# UP02513040.net
KiCad netlist of a schematic drawn in Altium Designer
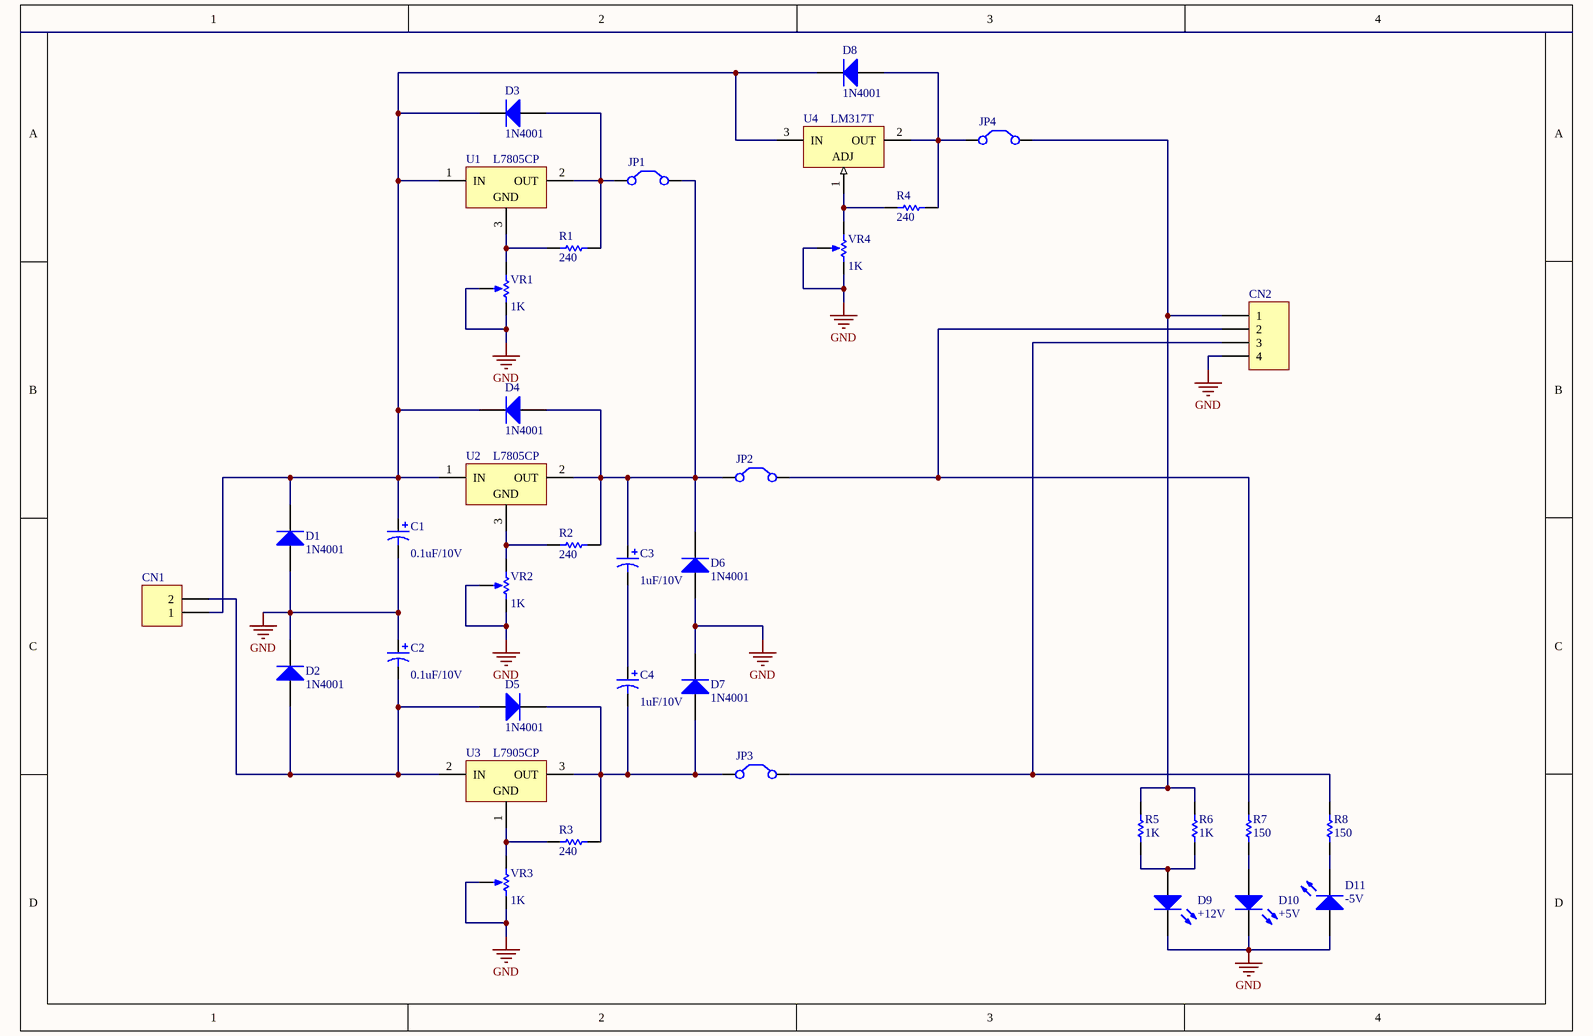
[diagram p0: UP02513040.SchDoc]

(export (version "E")
  (design (tool "Eeschema 10.0.6"))
  (components
    (comp (ref "C1")
      (value "0.1uF/10V")
      (footprint "RB7.6-15")
      (description "Polarized Capacitor (Radial)")
      (fields (field (name "Comment") "Cap Pol1") (field (name "PUBLISHER") "Altium Limited"))
      (libsource (lib "Miscellaneous Devices") (part "Cap Pol1"))
    )
    (comp (ref "C2")
      (value "0.1uF/10V")
      (footprint "RB7.6-15")
      (description "Polarized Capacitor (Radial)")
      (fields (field (name "Comment") "Cap Pol1") (field (name "PUBLISHER") "Altium Limited"))
      (libsource (lib "Miscellaneous Devices") (part "Cap Pol1"))
    )
    (comp (ref "C3")
      (value "1uF/10V")
      (footprint "RB7.6-15")
      (description "Polarized Capacitor (Radial)")
      (fields (field (name "Comment") "Cap Pol1") (field (name "PUBLISHER") "Altium Limited"))
      (libsource (lib "Miscellaneous Devices") (part "Cap Pol1"))
    )
    (comp (ref "C4")
      (value "1uF/10V")
      (footprint "RB7.6-15")
      (description "Polarized Capacitor (Radial)")
      (fields (field (name "Comment") "Cap Pol1") (field (name "PUBLISHER") "Altium Limited"))
      (libsource (lib "Miscellaneous Devices") (part "Cap Pol1"))
    )
    (comp (ref "CN1")
      (value "Header 2H")
      (footprint "HDR1X2H")
      (description "Header, 2-Pin, Right Angle")
      (fields
        (field (name "MANUFACTURER") "PHOENIX CONTACT")
        (field (name "MANUFACTURER PART NUMBER") "1725656")
        (field (name "PUBLISHER") "Altium Limited")
      )
      (libsource (lib "Miscellaneous Connectors") (part "Header 2H"))
    )
    (comp (ref "CN2")
      (value "Header 4H")
      (footprint "HDR1X4H")
      (description "Header, 4-Pin, Right Angle")
      (fields (field (name "PUBLISHER") "Altium Limited"))
      (libsource (lib "Miscellaneous Connectors") (part "Header 4H"))
    )
    (comp (ref "D1")
      (value "1N4001")
      (footprint "DO-41")
      (description "1 Amp General Purpose Rectifier")
      (fields
        (field (name "MANUFACTURER") "Micro Commercial Co")
        (field (name "MANUFACTURER PART NUMBER") "1N4001-TP")
        (field (name "PUBLISHER") "Altium Limited")
      )
      (libsource (lib "Miscellaneous Devices") (part "Diode 1N4001"))
    )
    (comp (ref "D2")
      (value "1N4001")
      (footprint "DO-41")
      (description "1 Amp General Purpose Rectifier")
      (fields
        (field (name "MANUFACTURER") "Micro Commercial Co")
        (field (name "MANUFACTURER PART NUMBER") "1N4001-TP")
        (field (name "PUBLISHER") "Altium Limited")
      )
      (libsource (lib "Miscellaneous Devices") (part "Diode 1N4001"))
    )
    (comp (ref "D3")
      (value "1N4001")
      (footprint "DO-41")
      (description "1 Amp General Purpose Rectifier")
      (fields
        (field (name "MANUFACTURER") "Micro Commercial Co")
        (field (name "MANUFACTURER PART NUMBER") "1N4001-TP")
        (field (name "PUBLISHER") "Altium Limited")
      )
      (libsource (lib "Miscellaneous Devices") (part "Diode 1N4001"))
    )
    (comp (ref "D4")
      (value "1N4001")
      (footprint "DO-41")
      (description "1 Amp General Purpose Rectifier")
      (fields
        (field (name "MANUFACTURER") "Micro Commercial Co")
        (field (name "MANUFACTURER PART NUMBER") "1N4001-TP")
        (field (name "PUBLISHER") "Altium Limited")
      )
      (libsource (lib "Miscellaneous Devices") (part "Diode 1N4001"))
    )
    (comp (ref "D5")
      (value "1N4001")
      (footprint "DO-41")
      (description "1 Amp General Purpose Rectifier")
      (fields
        (field (name "MANUFACTURER") "Micro Commercial Co")
        (field (name "MANUFACTURER PART NUMBER") "1N4001-TP")
        (field (name "PUBLISHER") "Altium Limited")
      )
      (libsource (lib "Miscellaneous Devices") (part "Diode 1N4001"))
    )
    (comp (ref "D6")
      (value "1N4001")
      (footprint "DO-41")
      (description "1 Amp General Purpose Rectifier")
      (fields
        (field (name "MANUFACTURER") "Micro Commercial Co")
        (field (name "MANUFACTURER PART NUMBER") "1N4001-TP")
        (field (name "PUBLISHER") "Altium Limited")
      )
      (libsource (lib "Miscellaneous Devices") (part "Diode 1N4001"))
    )
    (comp (ref "D7")
      (value "1N4001")
      (footprint "DO-41")
      (description "1 Amp General Purpose Rectifier")
      (fields
        (field (name "MANUFACTURER") "Micro Commercial Co")
        (field (name "MANUFACTURER PART NUMBER") "1N4001-TP")
        (field (name "PUBLISHER") "Altium Limited")
      )
      (libsource (lib "Miscellaneous Devices") (part "Diode 1N4001"))
    )
    (comp (ref "D8")
      (value "1N4001")
      (footprint "DO-41")
      (description "1 Amp General Purpose Rectifier")
      (fields
        (field (name "MANUFACTURER") "Micro Commercial Co")
        (field (name "MANUFACTURER PART NUMBER") "1N4001-TP")
        (field (name "PUBLISHER") "Altium Limited")
      )
      (libsource (lib "Miscellaneous Devices") (part "Diode 1N4001"))
    )
    (comp (ref "D9")
      (value "+12V")
      (footprint "LED-0")
      (description "Typical INFRARED GaAs LED")
      (fields
        (field (name "MANUFACTURER") "MULTICOMP")
        (field (name "MANUFACTURER PART NUMBER") "OVL-3324")
        (field (name "PUBLISHER") "Altium Limited")
      )
      (libsource (lib "Miscellaneous Devices") (part "LED0"))
    )
    (comp (ref "D10")
      (value "+5V")
      (footprint "LED-0")
      (description "Typical INFRARED GaAs LED")
      (fields
        (field (name "MANUFACTURER") "MULTICOMP")
        (field (name "MANUFACTURER PART NUMBER") "OVL-3324")
        (field (name "PUBLISHER") "Altium Limited")
      )
      (libsource (lib "Miscellaneous Devices") (part "LED0"))
    )
    (comp (ref "D11")
      (value "-5V")
      (footprint "LED-0")
      (description "Typical INFRARED GaAs LED")
      (fields
        (field (name "MANUFACTURER") "MULTICOMP")
        (field (name "MANUFACTURER PART NUMBER") "OVL-3324")
        (field (name "PUBLISHER") "Altium Limited")
      )
      (libsource (lib "Miscellaneous Devices") (part "LED0"))
    )
    (comp (ref "JP1")
      (value "Jumper")
      (footprint "RAD-0.2")
      (description "Jumper Wire")
      (fields
        (field (name "MANUFACTURER") "MULTICOMP")
        (field (name "MANUFACTURER PART NUMBER") "2211S-02G")
        (field (name "PUBLISHER") "Altium Limited")
      )
      (libsource (lib "Miscellaneous Devices") (part "Jumper"))
    )
    (comp (ref "JP2")
      (value "Jumper")
      (footprint "RAD-0.2")
      (description "Jumper Wire")
      (fields
        (field (name "MANUFACTURER") "MULTICOMP")
        (field (name "MANUFACTURER PART NUMBER") "2211S-02G")
        (field (name "PUBLISHER") "Altium Limited")
      )
      (libsource (lib "Miscellaneous Devices") (part "Jumper"))
    )
    (comp (ref "JP3")
      (value "Jumper")
      (footprint "RAD-0.2")
      (description "Jumper Wire")
      (fields
        (field (name "MANUFACTURER") "MULTICOMP")
        (field (name "MANUFACTURER PART NUMBER") "2211S-02G")
        (field (name "PUBLISHER") "Altium Limited")
      )
      (libsource (lib "Miscellaneous Devices") (part "Jumper"))
    )
    (comp (ref "JP4")
      (value "Jumper")
      (footprint "RAD-0.2")
      (description "Jumper Wire")
      (fields
        (field (name "MANUFACTURER") "MULTICOMP")
        (field (name "MANUFACTURER PART NUMBER") "2211S-02G")
        (field (name "PUBLISHER") "Altium Limited")
      )
      (libsource (lib "Miscellaneous Devices") (part "Jumper"))
    )
    (comp (ref "R1")
      (value "240")
      (footprint "AXIAL-0.3")
      (description "Resistor")
      (fields
        (field (name "MANUFACTURER") "NTE Electronics, Inc.")
        (field (name "MANUFACTURER PART NUMBER") "EW124")
        (field (name "PUBLISHER") "Altium Limited")
      )
      (libsource (lib "Miscellaneous Devices") (part "Res1"))
    )
    (comp (ref "R2")
      (value "240")
      (footprint "AXIAL-0.3")
      (description "Resistor")
      (fields
        (field (name "MANUFACTURER") "NTE Electronics, Inc.")
        (field (name "MANUFACTURER PART NUMBER") "EW124")
        (field (name "PUBLISHER") "Altium Limited")
      )
      (libsource (lib "Miscellaneous Devices") (part "Res1"))
    )
    (comp (ref "R3")
      (value "240")
      (footprint "AXIAL-0.3")
      (description "Resistor")
      (fields
        (field (name "MANUFACTURER") "NTE Electronics, Inc.")
        (field (name "MANUFACTURER PART NUMBER") "EW124")
        (field (name "PUBLISHER") "Altium Limited")
      )
      (libsource (lib "Miscellaneous Devices") (part "Res1"))
    )
    (comp (ref "R4")
      (value "240")
      (footprint "AXIAL-0.3")
      (description "Resistor")
      (fields
        (field (name "MANUFACTURER") "NTE Electronics, Inc.")
        (field (name "MANUFACTURER PART NUMBER") "EW124")
        (field (name "PUBLISHER") "Altium Limited")
      )
      (libsource (lib "Miscellaneous Devices") (part "Res1"))
    )
    (comp (ref "R5")
      (value "1K")
      (footprint "AXIAL-0.3")
      (description "Resistor")
      (fields
        (field (name "MANUFACTURER") "NTE Electronics, Inc.")
        (field (name "MANUFACTURER PART NUMBER") "EW124")
        (field (name "PUBLISHER") "Altium Limited")
      )
      (libsource (lib "Miscellaneous Devices") (part "Res1"))
    )
    (comp (ref "R6")
      (value "1K")
      (footprint "AXIAL-0.3")
      (description "Resistor")
      (fields
        (field (name "MANUFACTURER") "NTE Electronics, Inc.")
        (field (name "MANUFACTURER PART NUMBER") "EW124")
        (field (name "PUBLISHER") "Altium Limited")
      )
      (libsource (lib "Miscellaneous Devices") (part "Res1"))
    )
    (comp (ref "R7")
      (value "150")
      (footprint "AXIAL-0.3")
      (description "Resistor")
      (fields
        (field (name "MANUFACTURER") "NTE Electronics, Inc.")
        (field (name "MANUFACTURER PART NUMBER") "EW124")
        (field (name "PUBLISHER") "Altium Limited")
      )
      (libsource (lib "Miscellaneous Devices") (part "Res1"))
    )
    (comp (ref "R8")
      (value "150")
      (footprint "AXIAL-0.3")
      (description "Resistor")
      (fields
        (field (name "MANUFACTURER") "NTE Electronics, Inc.")
        (field (name "MANUFACTURER PART NUMBER") "EW124")
        (field (name "PUBLISHER") "Altium Limited")
      )
      (libsource (lib "Miscellaneous Devices") (part "Res1"))
    )
    (comp (ref "U1")
      (value "L7805CP")
      (footprint "ISOWATT220AB")
      (description "Positive Voltage Regulator")
      (fields
        (field (name "MANUFACTURER") "STMicroelectronics")
        (field (name "TOLERANCE") "5%")
        (field (name "PUBLISHER") "Altium Limited")
      )
      (libsource (lib "ST Power Mgt Voltage Regulator") (part "L7805CP"))
    )
    (comp (ref "U2")
      (value "L7805CP")
      (footprint "ISOWATT220AB")
      (description "Positive Voltage Regulator")
      (fields
        (field (name "MANUFACTURER") "STMicroelectronics")
        (field (name "TOLERANCE") "5%")
        (field (name "PUBLISHER") "Altium Limited")
      )
      (libsource (lib "ST Power Mgt Voltage Regulator") (part "L7805CP"))
    )
    (comp (ref "U3")
      (value "L7905CP")
      (footprint "ISOWATT220AB")
      (description "Negative Voltage Regulator")
      (fields (field (name "MANUFACTURER") "STMicroelectronics") (field (name "PUBLISHER") "Altium Limited"))
      (libsource (lib "ST Power Mgt Voltage Regulator") (part "L7905CP"))
    )
    (comp (ref "U4")
      (value "LM317T")
      (footprint "221A-04")
      (description "3-Terminal Adjustable Positive Voltage Regulator")
      (fields (field (name "PUBLISHER") "Altium Limited"))
      (libsource (lib "Motorola Power Mgt Voltage Regulator") (part "LM317T"))
    )
    (comp (ref "VR1")
      (value "1K")
      (footprint "VR5")
      (description "Potentiometer")
      (fields
        (field (name "MANUFACTURER") "BOURNS")
        (field (name "MANUFACTURER PART NUMBER") "3266W-1-103LF")
        (field (name "PUBLISHER") "Altium Limited")
      )
      (libsource (lib "Miscellaneous Devices") (part "RPot"))
    )
    (comp (ref "VR2")
      (value "1K")
      (footprint "VR5")
      (description "Potentiometer")
      (fields
        (field (name "MANUFACTURER") "BOURNS")
        (field (name "MANUFACTURER PART NUMBER") "3266W-1-103LF")
        (field (name "PUBLISHER") "Altium Limited")
      )
      (libsource (lib "Miscellaneous Devices") (part "RPot"))
    )
    (comp (ref "VR3")
      (value "1K")
      (footprint "VR5")
      (description "Potentiometer")
      (fields
        (field (name "MANUFACTURER") "BOURNS")
        (field (name "MANUFACTURER PART NUMBER") "3266W-1-103LF")
        (field (name "PUBLISHER") "Altium Limited")
      )
      (libsource (lib "Miscellaneous Devices") (part "RPot"))
    )
    (comp (ref "VR4")
      (value "1K")
      (footprint "VR5")
      (description "Potentiometer")
      (fields
        (field (name "MANUFACTURER") "BOURNS")
        (field (name "MANUFACTURER PART NUMBER") "3266W-1-103LF")
        (field (name "PUBLISHER") "Altium Limited")
      )
      (libsource (lib "Miscellaneous Devices") (part "RPot"))
    )
  )
  (nets
    (net (code "1") (name "GND") (class "Default")
      (node (ref "C1") (pin "2") (pinfunction "2_2") (pintype "passive"))
      (node (ref "C2") (pin "1") (pinfunction "1_1") (pintype "passive"))
      (node (ref "CN2") (pin "4") (pinfunction "4_4") (pintype "passive"))
      (node (ref "D1") (pin "1") (pinfunction "A_1") (pintype "passive"))
      (node (ref "D10") (pin "2") (pinfunction "K_2") (pintype "passive"))
      (node (ref "D11") (pin "1") (pinfunction "A_1") (pintype "passive"))
      (node (ref "D2") (pin "2") (pinfunction "K_2") (pintype "passive"))
      (node (ref "D6") (pin "1") (pinfunction "A_1") (pintype "passive"))
      (node (ref "D7") (pin "2") (pinfunction "K_2") (pintype "passive"))
      (node (ref "D9") (pin "2") (pinfunction "K_2") (pintype "passive"))
      (node (ref "VR1") (pin "2") (pinfunction "BOT_2") (pintype "passive"))
      (node (ref "VR1") (pin "3") (pinfunction "TAP_3") (pintype "passive"))
      (node (ref "VR2") (pin "2") (pinfunction "BOT_2") (pintype "passive"))
      (node (ref "VR2") (pin "3") (pinfunction "TAP_3") (pintype "passive"))
      (node (ref "VR3") (pin "2") (pinfunction "BOT_2") (pintype "passive"))
      (node (ref "VR3") (pin "3") (pinfunction "TAP_3") (pintype "passive"))
      (node (ref "VR4") (pin "2") (pinfunction "BOT_2") (pintype "passive"))
      (node (ref "VR4") (pin "3") (pinfunction "TAP_3") (pintype "passive"))
    )
    (net (code "2") (name "Net-(C3-Pad2)") (class "Default")
      (node (ref "C3") (pin "2") (pinfunction "2_2") (pintype "passive"))
      (node (ref "C4") (pin "1") (pinfunction "1_1") (pintype "passive"))
    )
    (net (code "3") (name "Net-(D1-K)") (class "Default")
      (node (ref "C1") (pin "1") (pinfunction "1_1") (pintype "passive"))
      (node (ref "CN1") (pin "1") (pinfunction "1_1") (pintype "passive"))
      (node (ref "D1") (pin "2") (pinfunction "K_2") (pintype "passive"))
      (node (ref "D3") (pin "2") (pinfunction "K_2") (pintype "passive"))
      (node (ref "D4") (pin "2") (pinfunction "K_2") (pintype "passive"))
      (node (ref "D8") (pin "2") (pinfunction "K_2") (pintype "passive"))
      (node (ref "U1") (pin "1") (pinfunction "IN_1") (pintype "power_in"))
      (node (ref "U2") (pin "1") (pinfunction "IN_1") (pintype "power_in"))
      (node (ref "U4") (pin "3") (pinfunction "IN_3") (pintype "power_in"))
    )
    (net (code "4") (name "Net-(D2-A)") (class "Default")
      (node (ref "C2") (pin "2") (pinfunction "2_2") (pintype "passive"))
      (node (ref "CN1") (pin "2") (pinfunction "2_2") (pintype "passive"))
      (node (ref "D2") (pin "1") (pinfunction "A_1") (pintype "passive"))
      (node (ref "D5") (pin "1") (pinfunction "A_1") (pintype "passive"))
      (node (ref "U3") (pin "2") (pinfunction "IN_2") (pintype "power_in"))
    )
    (net (code "5") (name "Net-(D3-A)") (class "Default")
      (node (ref "D3") (pin "1") (pinfunction "A_1") (pintype "passive"))
      (node (ref "JP1") (pin "1") (pinfunction "C1_1") (pintype "passive"))
      (node (ref "R1") (pin "1") (pinfunction "1_1") (pintype "passive"))
      (node (ref "U1") (pin "2") (pinfunction "OUT_2") (pintype "power_in"))
    )
    (net (code "6") (name "Net-(D4-A)") (class "Default")
      (node (ref "C3") (pin "1") (pinfunction "1_1") (pintype "passive"))
      (node (ref "D4") (pin "1") (pinfunction "A_1") (pintype "passive"))
      (node (ref "D6") (pin "2") (pinfunction "K_2") (pintype "passive"))
      (node (ref "JP1") (pin "2") (pinfunction "C2_2") (pintype "passive"))
      (node (ref "JP2") (pin "1") (pinfunction "C1_1") (pintype "passive"))
      (node (ref "R2") (pin "1") (pinfunction "1_1") (pintype "passive"))
      (node (ref "U2") (pin "2") (pinfunction "OUT_2") (pintype "power_in"))
    )
    (net (code "7") (name "Net-(D5-K)") (class "Default")
      (node (ref "C4") (pin "2") (pinfunction "2_2") (pintype "passive"))
      (node (ref "D5") (pin "2") (pinfunction "K_2") (pintype "passive"))
      (node (ref "D7") (pin "1") (pinfunction "A_1") (pintype "passive"))
      (node (ref "JP3") (pin "1") (pinfunction "C1_1") (pintype "passive"))
      (node (ref "R3") (pin "1") (pinfunction "1_1") (pintype "passive"))
      (node (ref "U3") (pin "3") (pinfunction "OUT_3") (pintype "power_in"))
    )
    (net (code "8") (name "Net-(D8-A)") (class "Default")
      (node (ref "D8") (pin "1") (pinfunction "A_1") (pintype "passive"))
      (node (ref "JP4") (pin "1") (pinfunction "C1_1") (pintype "passive"))
      (node (ref "R4") (pin "1") (pinfunction "1_1") (pintype "passive"))
      (node (ref "U4") (pin "2") (pinfunction "OUT_2") (pintype "power_in"))
    )
    (net (code "9") (name "Net-(D9-A)") (class "Default")
      (node (ref "D9") (pin "1") (pinfunction "A_1") (pintype "passive"))
      (node (ref "R5") (pin "2") (pinfunction "2_2") (pintype "passive"))
      (node (ref "R6") (pin "2") (pinfunction "2_2") (pintype "passive"))
    )
    (net (code "10") (name "Net-(D10-A)") (class "Default")
      (node (ref "D10") (pin "1") (pinfunction "A_1") (pintype "passive"))
      (node (ref "R7") (pin "2") (pinfunction "2_2") (pintype "passive"))
    )
    (net (code "11") (name "Net-(D11-K)") (class "Default")
      (node (ref "D11") (pin "2") (pinfunction "K_2") (pintype "passive"))
      (node (ref "R8") (pin "2") (pinfunction "2_2") (pintype "passive"))
    )
    (net (code "12") (name "Net-(JP2-C2)") (class "Default")
      (node (ref "CN2") (pin "2") (pinfunction "2_2") (pintype "passive"))
      (node (ref "JP2") (pin "2") (pinfunction "C2_2") (pintype "passive"))
      (node (ref "R7") (pin "1") (pinfunction "1_1") (pintype "passive"))
    )
    (net (code "13") (name "Net-(JP3-C2)") (class "Default")
      (node (ref "CN2") (pin "3") (pinfunction "3_3") (pintype "passive"))
      (node (ref "JP3") (pin "2") (pinfunction "C2_2") (pintype "passive"))
      (node (ref "R8") (pin "1") (pinfunction "1_1") (pintype "passive"))
    )
    (net (code "14") (name "Net-(JP4-C2)") (class "Default")
      (node (ref "CN2") (pin "1") (pinfunction "1_1") (pintype "passive"))
      (node (ref "JP4") (pin "2") (pinfunction "C2_2") (pintype "passive"))
      (node (ref "R5") (pin "1") (pinfunction "1_1") (pintype "passive"))
      (node (ref "R6") (pin "1") (pinfunction "1_1") (pintype "passive"))
    )
    (net (code "15") (name "Net-(U1-GND)") (class "Default")
      (node (ref "R1") (pin "2") (pinfunction "2_2") (pintype "passive"))
      (node (ref "U1") (pin "3") (pinfunction "GND_3") (pintype "power_in"))
      (node (ref "VR1") (pin "1") (pinfunction "TOP_1") (pintype "passive"))
    )
    (net (code "16") (name "Net-(U2-GND)") (class "Default")
      (node (ref "R2") (pin "2") (pinfunction "2_2") (pintype "passive"))
      (node (ref "U2") (pin "3") (pinfunction "GND_3") (pintype "power_in"))
      (node (ref "VR2") (pin "1") (pinfunction "TOP_1") (pintype "passive"))
    )
    (net (code "17") (name "Net-(U3-GND)") (class "Default")
      (node (ref "R3") (pin "2") (pinfunction "2_2") (pintype "passive"))
      (node (ref "U3") (pin "1") (pinfunction "GND_1") (pintype "power_in"))
      (node (ref "VR3") (pin "1") (pinfunction "TOP_1") (pintype "passive"))
    )
    (net (code "18") (name "Net-(U4-ADJ)") (class "Default")
      (node (ref "R4") (pin "2") (pinfunction "2_2") (pintype "passive"))
      (node (ref "U4") (pin "1") (pinfunction "ADJ_1") (pintype "input"))
      (node (ref "VR4") (pin "1") (pinfunction "TOP_1") (pintype "passive"))
    )
  )
)
